# 0_96OLED_SSD1306.net
KiCad netlist of a schematic drawn in Altium Designer
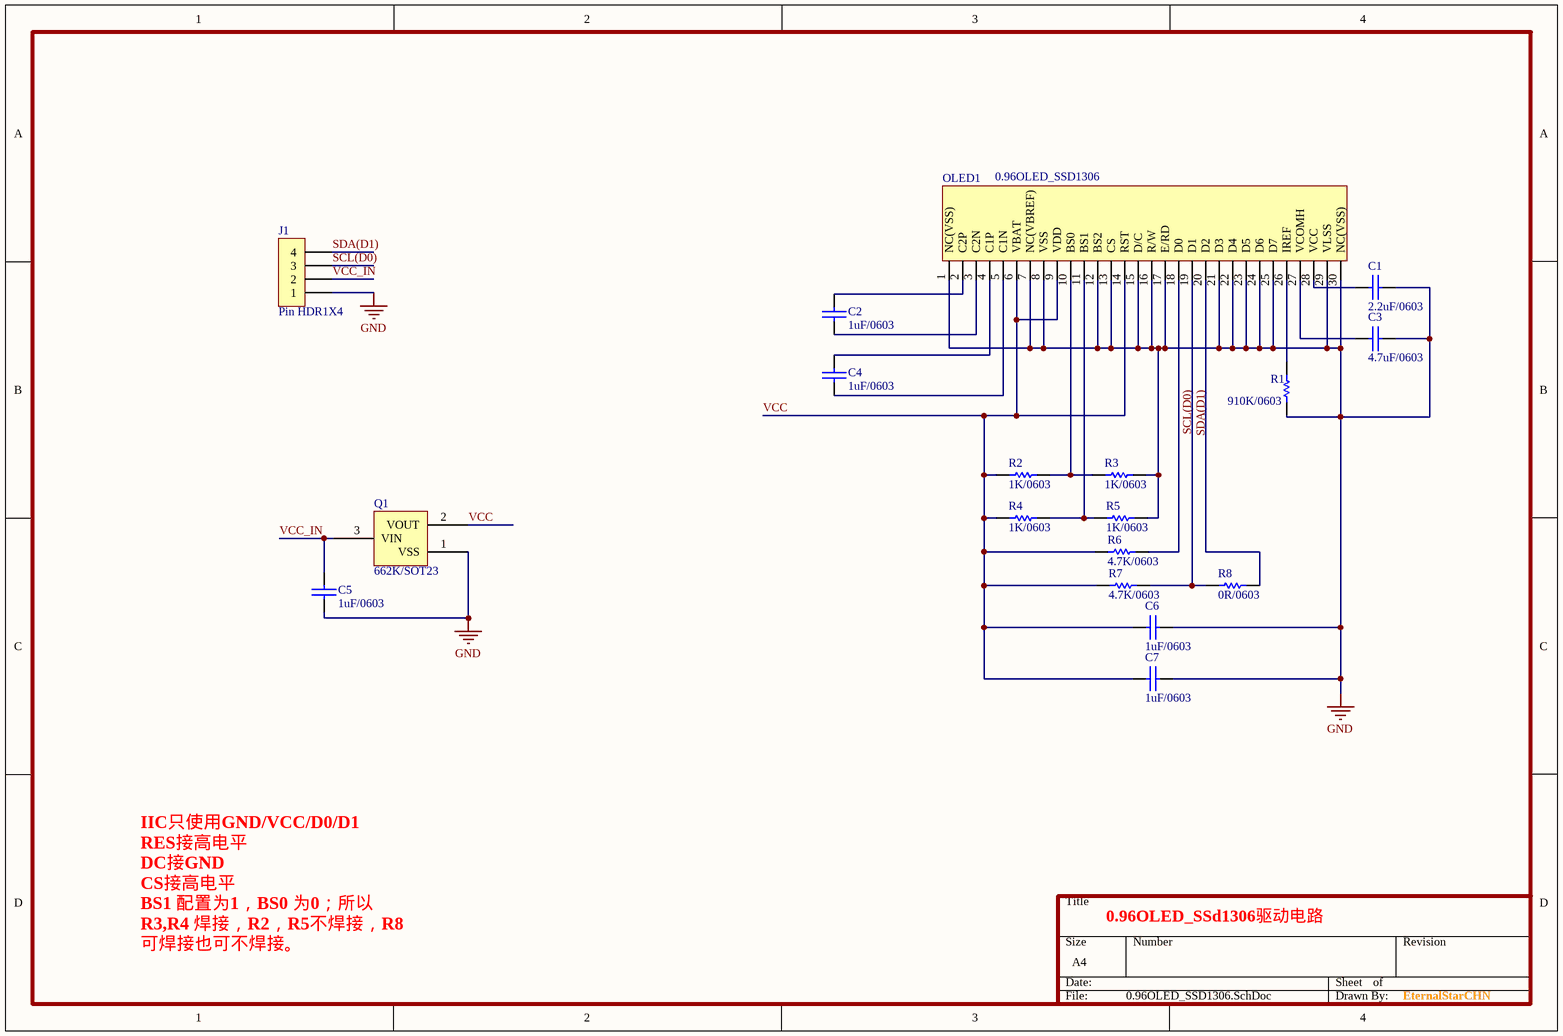
[diagram p0: 0.96OLED_SSD1306.SchDoc]

(export (version "E")
  (design (tool "Eeschema 10.0.6"))
  (components
    (comp (ref "C1")
      (value "2.2uF/0603")
      (footprint "0603C")
      (description "无极性电容")
      (libsource (lib "电容") (part "CAP"))
    )
    (comp (ref "C2")
      (value "1uF/0603")
      (footprint "0603C")
      (description "无极性电容")
      (libsource (lib "电容") (part "CAP"))
    )
    (comp (ref "C3")
      (value "4.7uF/0603")
      (footprint "0603C")
      (description "无极性电容")
      (libsource (lib "电容") (part "CAP"))
    )
    (comp (ref "C4")
      (value "1uF/0603")
      (footprint "0603C")
      (description "无极性电容")
      (libsource (lib "电容") (part "CAP"))
    )
    (comp (ref "C5")
      (value "1uF/0603")
      (footprint "0603C")
      (description "无极性电容")
      (libsource (lib "电容") (part "CAP"))
    )
    (comp (ref "C6")
      (value "1uF/0603")
      (footprint "0603C")
      (description "无极性电容")
      (libsource (lib "电容") (part "CAP"))
    )
    (comp (ref "C7")
      (value "1uF/0603")
      (footprint "0603C")
      (description "无极性电容")
      (libsource (lib "电容") (part "CAP"))
    )
    (comp (ref "J1")
      (value "Pin HDR1X4")
      (footprint "Pin HDR1X4/2.54mm-S")
      (libsource (lib "排针") (part "Pin HDR1X4"))
    )
    (comp (ref "OLED1")
      (value "0.96OLED_SSD1306")
      (footprint "OLED_0.96")
      (libsource (lib "LCD") (part "0.96OLED_SSD1306"))
    )
    (comp (ref "Q1")
      (value "662K/SOT23")
      (footprint "SOT23")
      (description "SOT23封装LDO")
      (libsource (lib "电源芯片") (part "LDO_SOT23"))
    )
    (comp (ref "R1") (value "910K/0603") (footprint "0603R") (libsource (lib "电阻") (part "RES")))
    (comp (ref "R2") (value "1K/0603") (footprint "0603R") (libsource (lib "电阻") (part "RES")))
    (comp (ref "R3") (value "1K/0603") (footprint "0603R") (libsource (lib "电阻") (part "RES")))
    (comp (ref "R4") (value "1K/0603") (footprint "0603R") (libsource (lib "电阻") (part "RES")))
    (comp (ref "R5") (value "1K/0603") (footprint "0603R") (libsource (lib "电阻") (part "RES")))
    (comp (ref "R6") (value "4.7K/0603") (footprint "0603R") (libsource (lib "电阻") (part "RES")))
    (comp (ref "R7") (value "4.7K/0603") (footprint "0603R") (libsource (lib "电阻") (part "RES")))
    (comp (ref "R8") (value "0R/0603") (footprint "0603R") (libsource (lib "电阻") (part "RES")))
  )
  (nets
    (net (code "1") (name "/SCL(D0)") (class "Default")
      (node (ref "J1") (pin "3") (pinfunction "3_3") (pintype "passive"))
      (node (ref "OLED1") (pin "18") (pinfunction "D0_18") (pintype "passive"))
      (node (ref "R6") (pin "1") (pinfunction "1_1") (pintype "passive"))
    )
    (net (code "2") (name "/SDA(D1)") (class "Default")
      (node (ref "J1") (pin "4") (pinfunction "4_4") (pintype "passive"))
      (node (ref "OLED1") (pin "19") (pinfunction "D1_19") (pintype "passive"))
      (node (ref "R7") (pin "1") (pinfunction "1_1") (pintype "passive"))
      (node (ref "R8") (pin "2") (pinfunction "2_2") (pintype "passive"))
    )
    (net (code "3") (name "/VCC") (class "Default")
      (node (ref "C6") (pin "2") (pinfunction "2_2") (pintype "passive"))
      (node (ref "C7") (pin "2") (pinfunction "2_2") (pintype "passive"))
      (node (ref "OLED1") (pin "14") (pinfunction "RST_14") (pintype "passive"))
      (node (ref "OLED1") (pin "6") (pinfunction "VBAT_6") (pintype "passive"))
      (node (ref "OLED1") (pin "9") (pinfunction "VDD_9") (pintype "passive"))
      (node (ref "Q1") (pin "2") (pinfunction "VOUT_2") (pintype "passive"))
      (node (ref "R2") (pin "2") (pinfunction "2_2") (pintype "passive"))
      (node (ref "R4") (pin "2") (pinfunction "2_2") (pintype "passive"))
      (node (ref "R6") (pin "2") (pinfunction "2_2") (pintype "passive"))
      (node (ref "R7") (pin "2") (pinfunction "2_2") (pintype "passive"))
    )
    (net (code "4") (name "/VCC_IN") (class "Default")
      (node (ref "C5") (pin "1") (pinfunction "1_1") (pintype "passive"))
      (node (ref "J1") (pin "2") (pinfunction "2_2") (pintype "passive"))
      (node (ref "Q1") (pin "3") (pinfunction "VIN_3") (pintype "passive"))
    )
    (net (code "5") (name "GND") (class "Default")
      (node (ref "C1") (pin "1") (pinfunction "1_1") (pintype "passive"))
      (node (ref "C3") (pin "1") (pinfunction "1_1") (pintype "passive"))
      (node (ref "C5") (pin "2") (pinfunction "2_2") (pintype "passive"))
      (node (ref "C6") (pin "1") (pinfunction "1_1") (pintype "passive"))
      (node (ref "C7") (pin "1") (pinfunction "1_1") (pintype "passive"))
      (node (ref "J1") (pin "1") (pinfunction "1_1") (pintype "passive"))
      (node (ref "OLED1") (pin "1") (pinfunction "NC(VSS)_1") (pintype "passive"))
      (node (ref "OLED1") (pin "12") (pinfunction "BS2_12") (pintype "passive"))
      (node (ref "OLED1") (pin "13") (pinfunction "CS_13") (pintype "passive"))
      (node (ref "OLED1") (pin "15") (pinfunction "D/C_15") (pintype "passive"))
      (node (ref "OLED1") (pin "16") (pinfunction "R/W_16") (pintype "passive"))
      (node (ref "OLED1") (pin "17") (pinfunction "E/RD_17") (pintype "passive"))
      (node (ref "OLED1") (pin "21") (pinfunction "D3_21") (pintype "passive"))
      (node (ref "OLED1") (pin "22") (pinfunction "D4_22") (pintype "passive"))
      (node (ref "OLED1") (pin "23") (pinfunction "D5_23") (pintype "passive"))
      (node (ref "OLED1") (pin "24") (pinfunction "D6_24") (pintype "passive"))
      (node (ref "OLED1") (pin "25") (pinfunction "D7_25") (pintype "passive"))
      (node (ref "OLED1") (pin "29") (pinfunction "VLSS_29") (pintype "passive"))
      (node (ref "OLED1") (pin "30") (pinfunction "NC(VSS)_30") (pintype "passive"))
      (node (ref "OLED1") (pin "7") (pinfunction "NC(VBREF)_7") (pintype "passive"))
      (node (ref "OLED1") (pin "8") (pinfunction "VSS_8") (pintype "passive"))
      (node (ref "Q1") (pin "1") (pinfunction "VSS_1") (pintype "passive"))
      (node (ref "R1") (pin "1") (pinfunction "1_1") (pintype "passive"))
      (node (ref "R3") (pin "1") (pinfunction "1_1") (pintype "passive"))
      (node (ref "R5") (pin "1") (pinfunction "1_1") (pintype "passive"))
    )
    (net (code "6") (name "Net-(OLED1-BS0)") (class "Default")
      (node (ref "OLED1") (pin "10") (pinfunction "BS0_10") (pintype "passive"))
      (node (ref "R2") (pin "1") (pinfunction "1_1") (pintype "passive"))
      (node (ref "R3") (pin "2") (pinfunction "2_2") (pintype "passive"))
    )
    (net (code "7") (name "Net-(OLED1-BS1)") (class "Default")
      (node (ref "OLED1") (pin "11") (pinfunction "BS1_11") (pintype "passive"))
      (node (ref "R4") (pin "1") (pinfunction "1_1") (pintype "passive"))
      (node (ref "R5") (pin "2") (pinfunction "2_2") (pintype "passive"))
    )
    (net (code "8") (name "Net-(OLED1-C1N)") (class "Default")
      (node (ref "C4") (pin "1") (pinfunction "1_1") (pintype "passive"))
      (node (ref "OLED1") (pin "5") (pinfunction "C1N_5") (pintype "passive"))
    )
    (net (code "9") (name "Net-(OLED1-C1P)") (class "Default")
      (node (ref "C4") (pin "2") (pinfunction "2_2") (pintype "passive"))
      (node (ref "OLED1") (pin "4") (pinfunction "C1P_4") (pintype "passive"))
    )
    (net (code "10") (name "Net-(OLED1-C2N)") (class "Default")
      (node (ref "C2") (pin "1") (pinfunction "1_1") (pintype "passive"))
      (node (ref "OLED1") (pin "3") (pinfunction "C2N_3") (pintype "passive"))
    )
    (net (code "11") (name "Net-(OLED1-C2P)") (class "Default")
      (node (ref "C2") (pin "2") (pinfunction "2_2") (pintype "passive"))
      (node (ref "OLED1") (pin "2") (pinfunction "C2P_2") (pintype "passive"))
    )
    (net (code "12") (name "Net-(OLED1-D2)") (class "Default")
      (node (ref "OLED1") (pin "20") (pinfunction "D2_20") (pintype "passive"))
      (node (ref "R8") (pin "1") (pinfunction "1_1") (pintype "passive"))
    )
    (net (code "13") (name "Net-(OLED1-IREF)") (class "Default")
      (node (ref "OLED1") (pin "26") (pinfunction "IREF_26") (pintype "passive"))
      (node (ref "R1") (pin "2") (pinfunction "2_2") (pintype "passive"))
    )
    (net (code "14") (name "Net-(OLED1-VCC)") (class "Default")
      (node (ref "C1") (pin "2") (pinfunction "2_2") (pintype "passive"))
      (node (ref "OLED1") (pin "28") (pinfunction "VCC_28") (pintype "passive"))
    )
    (net (code "15") (name "Net-(OLED1-VCOMH)") (class "Default")
      (node (ref "C3") (pin "2") (pinfunction "2_2") (pintype "passive"))
      (node (ref "OLED1") (pin "27") (pinfunction "VCOMH_27") (pintype "passive"))
    )
  )
)
